# ESP-XBee_v0_1.net
KiCad netlist of a schematic drawn in EAGLE
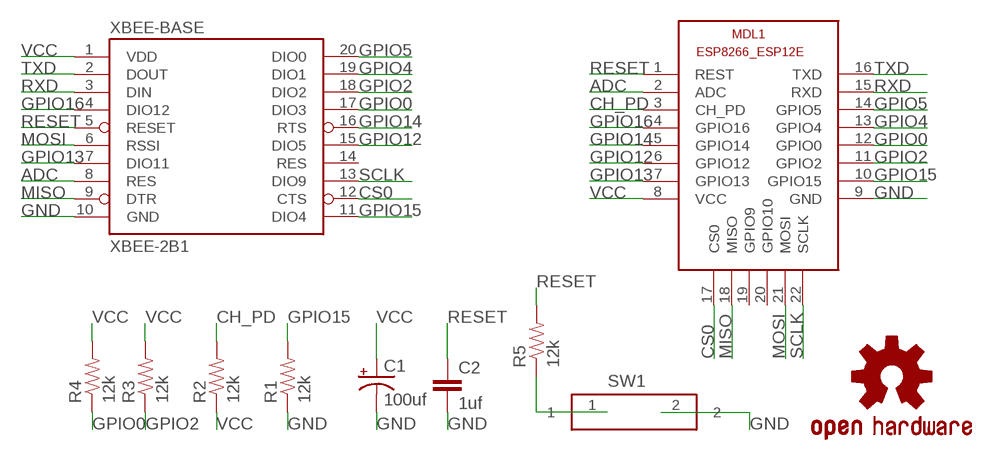
[diagram p0: schematic, sheet 1]

(export (version "E")
  (design (tool "Eeschema 10.0.6"))
  (components
    (comp (ref "C1")
      (value "100uf")
      (footprint "eagle-import:EIA3216-KIT")
      (libsource (lib "eagle-import") (part "CAP_POL1206-KIT"))
    )
    (comp (ref "C2")
      (value "1uf")
      (footprint "eagle-import:0805")
      (libsource (lib "eagle-import") (part "CAP0805"))
    )
    (comp (ref "LOGO3")
      (value "OSHW-LOGOS")
      (footprint "eagle-import:OSHW-LOGO-S")
      (libsource (lib "eagle-import") (part "OSHW-LOGOS"))
    )
    (comp (ref "MDL1")
      (value "ESP8266-12EESP8266-ESP12E")
      (footprint "eagle-import:ESP8266-ESP12E")
      (libsource (lib "eagle-import") (part "ESP8266-12EESP8266-ESP12E"))
    )
    (comp (ref "R1")
      (value "12k")
      (footprint "eagle-import:0805")
      (libsource (lib "eagle-import") (part "RESISTOR0805-RES"))
    )
    (comp (ref "R2")
      (value "12k")
      (footprint "eagle-import:0805")
      (libsource (lib "eagle-import") (part "RESISTOR0805-RES"))
    )
    (comp (ref "R3")
      (value "12k")
      (footprint "eagle-import:0805")
      (libsource (lib "eagle-import") (part "RESISTOR0805-RES"))
    )
    (comp (ref "R4")
      (value "12k")
      (footprint "eagle-import:0805")
      (libsource (lib "eagle-import") (part "RESISTOR0805-RES"))
    )
    (comp (ref "R5")
      (value "12k")
      (footprint "eagle-import:0805")
      (libsource (lib "eagle-import") (part "RESISTOR0805-RES"))
    )
    (comp (ref "SW1")
      (value "434111043826")
      (footprint "eagle-import:434111043826")
      (libsource (lib "eagle-import") (part "434111043826"))
    )
    (comp (ref "XBEE-BASE")
      (value "XBEE-2B1")
      (footprint "eagle-import:XBEE-1")
      (libsource (lib "eagle-import") (part "XBEE-2B1"))
    )
  )
  (nets
    (net (code "1") (name "/ADC") (class "Default")
      (node (ref "MDL1") (pin "2") (pinfunction "ADC_2") (pintype "bidirectional"))
      (node (ref "XBEE-BASE") (pin "8") (pinfunction "RES_8") (pintype "bidirectional"))
    )
    (net (code "2") (name "/CH_PD") (class "Default")
      (node (ref "MDL1") (pin "3") (pinfunction "CH_PD_3") (pintype "bidirectional"))
      (node (ref "R2") (pin "2") (pinfunction "2_2") (pintype "passive"))
    )
    (net (code "3") (name "/CS0") (class "Default")
      (node (ref "MDL1") (pin "17") (pinfunction "CS0_17") (pintype "bidirectional"))
      (node (ref "XBEE-BASE") (pin "12") (pinfunction "CTS_12") (pintype "output"))
    )
    (net (code "4") (name "/GND") (class "Default")
      (node (ref "C1") (pin "C") (pinfunction "-_C") (pintype "passive"))
      (node (ref "C2") (pin "2") (pinfunction "2_2") (pintype "passive"))
      (node (ref "MDL1") (pin "9") (pinfunction "GND_9") (pintype "bidirectional"))
      (node (ref "R1") (pin "1") (pinfunction "1_1") (pintype "passive"))
      (node (ref "SW1") (pin "2") (pinfunction "2_2") (pintype "bidirectional"))
      (node (ref "XBEE-BASE") (pin "10") (pinfunction "GND_10") (pintype "power_in"))
    )
    (net (code "5") (name "/GPIO0") (class "Default")
      (node (ref "MDL1") (pin "12") (pinfunction "GPIO0_12") (pintype "bidirectional"))
      (node (ref "R4") (pin "1") (pinfunction "1_1") (pintype "passive"))
      (node (ref "XBEE-BASE") (pin "17") (pinfunction "DIO3_17") (pintype "bidirectional"))
    )
    (net (code "6") (name "/GPIO2") (class "Default")
      (node (ref "MDL1") (pin "11") (pinfunction "GPIO2_11") (pintype "bidirectional"))
      (node (ref "R3") (pin "1") (pinfunction "1_1") (pintype "passive"))
      (node (ref "XBEE-BASE") (pin "18") (pinfunction "DIO2_18") (pintype "bidirectional"))
    )
    (net (code "7") (name "/GPIO4") (class "Default")
      (node (ref "MDL1") (pin "13") (pinfunction "GPIO4_13") (pintype "bidirectional"))
      (node (ref "XBEE-BASE") (pin "19") (pinfunction "DIO1_19") (pintype "bidirectional"))
    )
    (net (code "8") (name "/GPIO5") (class "Default")
      (node (ref "MDL1") (pin "14") (pinfunction "GPIO5_14") (pintype "bidirectional"))
      (node (ref "XBEE-BASE") (pin "20") (pinfunction "DIO0_20") (pintype "bidirectional"))
    )
    (net (code "9") (name "/GPIO12") (class "Default")
      (node (ref "MDL1") (pin "6") (pinfunction "GPIO12_6") (pintype "bidirectional"))
      (node (ref "XBEE-BASE") (pin "15") (pinfunction "DIO5_15") (pintype "bidirectional"))
    )
    (net (code "10") (name "/GPIO13") (class "Default")
      (node (ref "MDL1") (pin "7") (pinfunction "GPIO13_7") (pintype "bidirectional"))
      (node (ref "XBEE-BASE") (pin "7") (pinfunction "DIO11_7") (pintype "bidirectional"))
    )
    (net (code "11") (name "/GPIO14") (class "Default")
      (node (ref "MDL1") (pin "5") (pinfunction "GPIO14_5") (pintype "bidirectional"))
      (node (ref "XBEE-BASE") (pin "16") (pinfunction "RTS_16") (pintype "input"))
    )
    (net (code "12") (name "/GPIO15") (class "Default")
      (node (ref "MDL1") (pin "10") (pinfunction "GPIO15_10") (pintype "bidirectional"))
      (node (ref "R1") (pin "2") (pinfunction "2_2") (pintype "passive"))
      (node (ref "XBEE-BASE") (pin "11") (pinfunction "DIO4_11") (pintype "bidirectional"))
    )
    (net (code "13") (name "/GPIO16") (class "Default")
      (node (ref "MDL1") (pin "4") (pinfunction "GPIO16_4") (pintype "bidirectional"))
      (node (ref "XBEE-BASE") (pin "4") (pinfunction "DIO12_4") (pintype "bidirectional"))
    )
    (net (code "14") (name "/MISO") (class "Default")
      (node (ref "MDL1") (pin "18") (pinfunction "MISO_18") (pintype "bidirectional"))
      (node (ref "XBEE-BASE") (pin "9") (pinfunction "DTR_9") (pintype "bidirectional"))
    )
    (net (code "15") (name "/MOSI") (class "Default")
      (node (ref "MDL1") (pin "21") (pinfunction "MOSI_21") (pintype "bidirectional"))
      (node (ref "XBEE-BASE") (pin "6") (pinfunction "RSSI_6") (pintype "bidirectional"))
    )
    (net (code "16") (name "/RESET") (class "Default")
      (node (ref "C2") (pin "1") (pinfunction "1_1") (pintype "passive"))
      (node (ref "MDL1") (pin "1") (pinfunction "REST_1") (pintype "bidirectional"))
      (node (ref "R5") (pin "2") (pinfunction "2_2") (pintype "passive"))
      (node (ref "XBEE-BASE") (pin "5") (pinfunction "RESET_5") (pintype "input"))
    )
    (net (code "17") (name "/RXD") (class "Default")
      (node (ref "MDL1") (pin "15") (pinfunction "RXD_15") (pintype "bidirectional"))
      (node (ref "XBEE-BASE") (pin "3") (pinfunction "DIN_3") (pintype "input"))
    )
    (net (code "18") (name "/SCLK") (class "Default")
      (node (ref "MDL1") (pin "22") (pinfunction "SCLK_22") (pintype "bidirectional"))
      (node (ref "XBEE-BASE") (pin "13") (pinfunction "DIO9_13") (pintype "bidirectional"))
    )
    (net (code "19") (name "/TXD") (class "Default")
      (node (ref "MDL1") (pin "16") (pinfunction "TXD_16") (pintype "bidirectional"))
      (node (ref "XBEE-BASE") (pin "2") (pinfunction "DOUT_2") (pintype "output"))
    )
    (net (code "20") (name "/VCC") (class "Default")
      (node (ref "C1") (pin "A") (pinfunction "+_A") (pintype "passive"))
      (node (ref "MDL1") (pin "8") (pinfunction "VCC_8") (pintype "bidirectional"))
      (node (ref "R2") (pin "1") (pinfunction "1_1") (pintype "passive"))
      (node (ref "R3") (pin "2") (pinfunction "2_2") (pintype "passive"))
      (node (ref "R4") (pin "2") (pinfunction "2_2") (pintype "passive"))
      (node (ref "XBEE-BASE") (pin "1") (pinfunction "VDD_1") (pintype "power_in"))
    )
    (net (code "21") (name "Net-(R5-Pad1)") (class "Default")
      (node (ref "R5") (pin "1") (pinfunction "1_1") (pintype "passive"))
      (node (ref "SW1") (pin "1") (pinfunction "1_1") (pintype "bidirectional"))
    )
    (net (code "22") (name "unconnected-(MDL1-GPIO9-Pad19)") (class "Default")
      (node (ref "MDL1") (pin "19") (pinfunction "GPIO9_19") (pintype "bidirectional"))
    )
    (net (code "23") (name "unconnected-(MDL1-GPIO10-Pad20)") (class "Default")
      (node (ref "MDL1") (pin "20") (pinfunction "GPIO10_20") (pintype "bidirectional"))
    )
    (net (code "24") (name "unconnected-(XBEE-BASE-RES-Pad14)") (class "Default")
      (node (ref "XBEE-BASE") (pin "14") (pinfunction "RES_14") (pintype "bidirectional"))
    )
  )
)
